# espiotv1.net
KiCad netlist of a schematic drawn in EAGLE
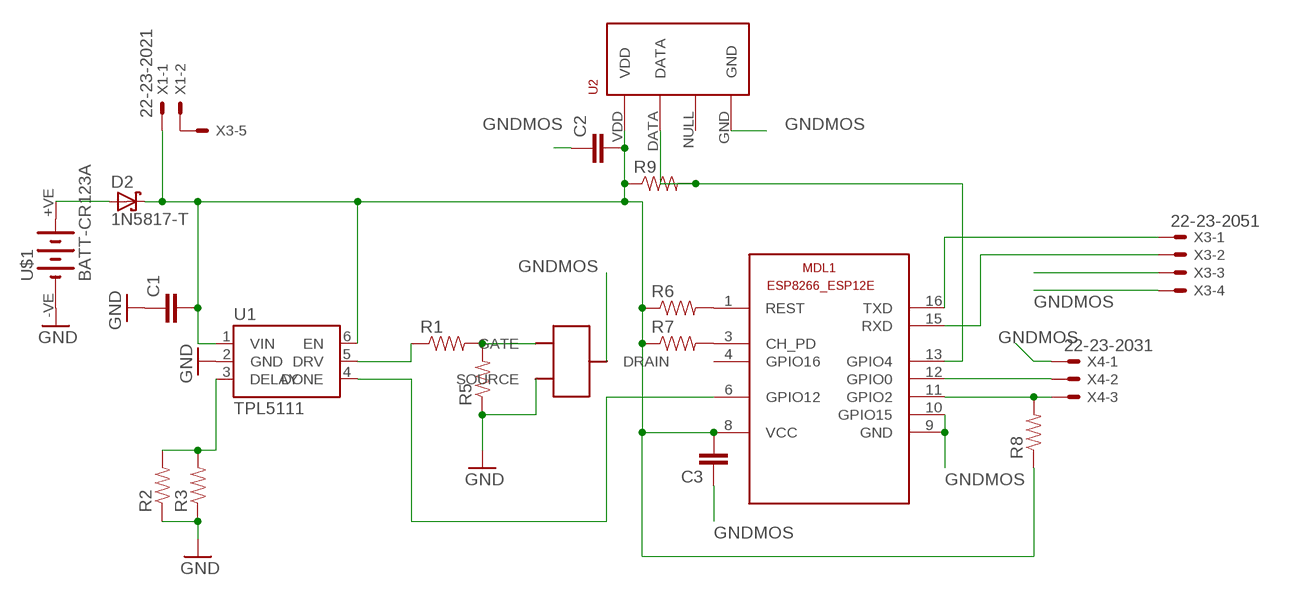
[diagram p0: schematic, sheet 1]

(export (version "E")
  (design (tool "Eeschema 10.0.6"))
  (components
    (comp (ref "C1")
      (value "CAP0603-CAP")
      (footprint "eagle-import:0603-CAP")
      (libsource (lib "eagle-import") (part "CAP0603-CAP"))
    )
    (comp (ref "C2")
      (value "CAP0603-CAP")
      (footprint "eagle-import:0603-CAP")
      (libsource (lib "eagle-import") (part "CAP0603-CAP"))
    )
    (comp (ref "C3")
      (value "CAP0603-CAP")
      (footprint "eagle-import:0603-CAP")
      (libsource (lib "eagle-import") (part "CAP0603-CAP"))
    )
    (comp (ref "D2")
      (value "1N5817-T")
      (footprint "eagle-import:DO41-7.6")
      (libsource (lib "eagle-import") (part "1N5817-T"))
    )
    (comp (ref "MDL1")
      (value "ESP8266-12EESP8266-ESP12E")
      (footprint "eagle-import:ESP8266-ESP12E")
      (libsource (lib "eagle-import") (part "ESP8266-12EESP8266-ESP12E"))
    )
    (comp (ref "R1")
      (value "RESISTOR0603-RES")
      (footprint "eagle-import:0603-RES")
      (libsource (lib "eagle-import") (part "RESISTOR0603-RES"))
    )
    (comp (ref "R2")
      (value "RESISTOR0603-RES")
      (footprint "eagle-import:0603-RES")
      (libsource (lib "eagle-import") (part "RESISTOR0603-RES"))
    )
    (comp (ref "R3")
      (value "RESISTOR0603-RES")
      (footprint "eagle-import:0603-RES")
      (libsource (lib "eagle-import") (part "RESISTOR0603-RES"))
    )
    (comp (ref "R5")
      (value "RESISTOR0603-RES")
      (footprint "eagle-import:0603-RES")
      (libsource (lib "eagle-import") (part "RESISTOR0603-RES"))
    )
    (comp (ref "R6")
      (value "RESISTOR0603-RES")
      (footprint "eagle-import:0603-RES")
      (libsource (lib "eagle-import") (part "RESISTOR0603-RES"))
    )
    (comp (ref "R7")
      (value "RESISTOR0603-RES")
      (footprint "eagle-import:0603-RES")
      (libsource (lib "eagle-import") (part "RESISTOR0603-RES"))
    )
    (comp (ref "R8")
      (value "RESISTOR0603-RES")
      (footprint "eagle-import:0603-RES")
      (libsource (lib "eagle-import") (part "RESISTOR0603-RES"))
    )
    (comp (ref "R9")
      (value "RESISTOR0603-RES")
      (footprint "eagle-import:0603-RES")
      (libsource (lib "eagle-import") (part "RESISTOR0603-RES"))
    )
    (comp (ref "U$1")
      (value "BATT-CR123A")
      (footprint "eagle-import:KEYSTONE-2_3A")
      (libsource (lib "eagle-import") (part "BATT-CR123A"))
    )
    (comp (ref "U$3")
      (value "IRLML2502")
      (footprint "eagle-import:IRLML2502")
      (libsource (lib "eagle-import") (part "IRLML2502"))
    )
    (comp (ref "U1")
      (value "TPL5111")
      (footprint "eagle-import:SOT23-6")
      (libsource (lib "eagle-import") (part "TPL5111SOT-23"))
    )
    (comp (ref "U2")
      (value "RHT03_DHT-22_AM2302RA")
      (footprint "eagle-import:RHT03_DHT-22_RA")
      (libsource (lib "eagle-import") (part "RHT03_DHT-22_AM2302RA"))
    )
    (comp (ref "X1")
      (value "22-23-2021")
      (footprint "eagle-import:22-23-2021")
      (fields (field (name "MF") "MOLEX"))
      (libsource (lib "eagle-import") (part "22-23-2021"))
    )
    (comp (ref "X3")
      (value "22-23-2051")
      (footprint "eagle-import:22-23-2051")
      (fields (field (name "MF") "MOLEX"))
      (libsource (lib "eagle-import") (part "22-23-2051"))
    )
    (comp (ref "X4")
      (value "22-23-2031")
      (footprint "eagle-import:22-23-2031")
      (fields (field (name "MF") "MOLEX"))
      (libsource (lib "eagle-import") (part "22-23-2031"))
    )
  )
  (nets
    (net (code "1") (name "/GNDMOS") (class "Default")
      (node (ref "C2") (pin "1") (pinfunction "1_1") (pintype "passive"))
      (node (ref "C3") (pin "1") (pinfunction "1_1") (pintype "passive"))
      (node (ref "MDL1") (pin "10") (pinfunction "GPIO15_10") (pintype "bidirectional"))
      (node (ref "MDL1") (pin "9") (pinfunction "GND_9") (pintype "bidirectional"))
      (node (ref "U$3") (pin "D") (pinfunction "DRAIN_D") (pintype "bidirectional"))
      (node (ref "U2") (pin "GND") (pinfunction "GND_GND") (pintype "power_in"))
      (node (ref "X3") (pin "3") (pinfunction "S_3") (pintype "passive"))
      (node (ref "X3") (pin "4") (pinfunction "S_4") (pintype "passive"))
      (node (ref "X4") (pin "1") (pinfunction "S_1") (pintype "passive"))
    )
    (net (code "2") (name "GND") (class "Default")
      (node (ref "C1") (pin "1") (pinfunction "1_1") (pintype "passive"))
      (node (ref "R2") (pin "1") (pinfunction "1_1") (pintype "passive"))
      (node (ref "R3") (pin "1") (pinfunction "1_1") (pintype "passive"))
      (node (ref "R5") (pin "1") (pinfunction "1_1") (pintype "passive"))
      (node (ref "U$1") (pin "-VE") (pinfunction "-_-VE") (pintype "passive"))
      (node (ref "U$3") (pin "S") (pinfunction "SOURCE_S") (pintype "bidirectional"))
      (node (ref "U1") (pin "2") (pinfunction "GND_2") (pintype "bidirectional"))
    )
    (net (code "3") (name "Net-(MDL1-CH_PD)") (class "Default")
      (node (ref "MDL1") (pin "3") (pinfunction "CH_PD_3") (pintype "bidirectional"))
      (node (ref "R7") (pin "2") (pinfunction "2_2") (pintype "passive"))
    )
    (net (code "4") (name "Net-(MDL1-GPIO0)") (class "Default")
      (node (ref "MDL1") (pin "12") (pinfunction "GPIO0_12") (pintype "bidirectional"))
      (node (ref "X4") (pin "2") (pinfunction "S_2") (pintype "passive"))
    )
    (net (code "5") (name "Net-(MDL1-GPIO2)") (class "Default")
      (node (ref "MDL1") (pin "11") (pinfunction "GPIO2_11") (pintype "bidirectional"))
      (node (ref "R8") (pin "2") (pinfunction "2_2") (pintype "passive"))
      (node (ref "X4") (pin "3") (pinfunction "S_3") (pintype "passive"))
    )
    (net (code "6") (name "Net-(MDL1-GPIO4)") (class "Default")
      (node (ref "MDL1") (pin "13") (pinfunction "GPIO4_13") (pintype "bidirectional"))
      (node (ref "R9") (pin "2") (pinfunction "2_2") (pintype "passive"))
      (node (ref "U2") (pin "DATA") (pinfunction "DATA_DATA") (pintype "bidirectional"))
    )
    (net (code "7") (name "Net-(MDL1-GPIO12)") (class "Default")
      (node (ref "MDL1") (pin "6") (pinfunction "GPIO12_6") (pintype "bidirectional"))
      (node (ref "U1") (pin "4") (pinfunction "DONE_4") (pintype "bidirectional"))
    )
    (net (code "8") (name "Net-(MDL1-REST)") (class "Default")
      (node (ref "MDL1") (pin "1") (pinfunction "REST_1") (pintype "bidirectional"))
      (node (ref "R6") (pin "2") (pinfunction "2_2") (pintype "passive"))
    )
    (net (code "9") (name "Net-(MDL1-RXD)") (class "Default")
      (node (ref "MDL1") (pin "15") (pinfunction "RXD_15") (pintype "bidirectional"))
      (node (ref "X3") (pin "2") (pinfunction "S_2") (pintype "passive"))
    )
    (net (code "10") (name "Net-(MDL1-TXD)") (class "Default")
      (node (ref "MDL1") (pin "16") (pinfunction "TXD_16") (pintype "bidirectional"))
      (node (ref "X3") (pin "1") (pinfunction "S_1") (pintype "passive"))
    )
    (net (code "11") (name "Net-(MDL1-VCC)") (class "Default")
      (node (ref "C1") (pin "2") (pinfunction "2_2") (pintype "passive"))
      (node (ref "C2") (pin "2") (pinfunction "2_2") (pintype "passive"))
      (node (ref "C3") (pin "2") (pinfunction "2_2") (pintype "passive"))
      (node (ref "D2") (pin "C") (pinfunction "C_C") (pintype "passive"))
      (node (ref "MDL1") (pin "8") (pinfunction "VCC_8") (pintype "bidirectional"))
      (node (ref "R6") (pin "1") (pinfunction "1_1") (pintype "passive"))
      (node (ref "R7") (pin "1") (pinfunction "1_1") (pintype "passive"))
      (node (ref "R8") (pin "1") (pinfunction "1_1") (pintype "passive"))
      (node (ref "R9") (pin "1") (pinfunction "1_1") (pintype "passive"))
      (node (ref "U1") (pin "1") (pinfunction "VIN_1") (pintype "bidirectional"))
      (node (ref "U1") (pin "6") (pinfunction "EN_6") (pintype "bidirectional"))
      (node (ref "U2") (pin "VDD") (pinfunction "VDD_VDD") (pintype "power_in"))
      (node (ref "X1") (pin "1") (pinfunction "S_1") (pintype "passive"))
    )
    (net (code "12") (name "Net-(U$1-+)") (class "Default")
      (node (ref "D2") (pin "A") (pinfunction "A_A") (pintype "passive"))
      (node (ref "U$1") (pin "+VE") (pinfunction "+_+VE") (pintype "passive"))
    )
    (net (code "13") (name "Net-(U$3-GATE)") (class "Default")
      (node (ref "R1") (pin "2") (pinfunction "2_2") (pintype "passive"))
      (node (ref "R5") (pin "2") (pinfunction "2_2") (pintype "passive"))
      (node (ref "U$3") (pin "G") (pinfunction "GATE_G") (pintype "bidirectional"))
    )
    (net (code "14") (name "Net-(U1-DELAY)") (class "Default")
      (node (ref "R2") (pin "2") (pinfunction "2_2") (pintype "passive"))
      (node (ref "R3") (pin "2") (pinfunction "2_2") (pintype "passive"))
      (node (ref "U1") (pin "3") (pinfunction "DELAY_3") (pintype "bidirectional"))
    )
    (net (code "15") (name "Net-(U1-DRV)") (class "Default")
      (node (ref "R1") (pin "1") (pinfunction "1_1") (pintype "passive"))
      (node (ref "U1") (pin "5") (pinfunction "DRV_5") (pintype "bidirectional"))
    )
    (net (code "16") (name "Net-(X1B-S)") (class "Default")
      (node (ref "X1") (pin "2") (pinfunction "S_2") (pintype "passive"))
      (node (ref "X3") (pin "5") (pinfunction "S_5") (pintype "passive"))
    )
    (net (code "17") (name "unconnected-(MDL1-GPIO16-Pad4)") (class "Default")
      (node (ref "MDL1") (pin "4") (pinfunction "GPIO16_4") (pintype "bidirectional"))
    )
    (net (code "18") (name "unconnected-(U2-PadNULL)") (class "Default")
      (node (ref "U2") (pin "NULL") (pinfunction "NULL_NULL") (pintype "no_connect"))
    )
  )
)
